# Adapter_v1_0B.net
KiCad netlist of a schematic drawn in EAGLE
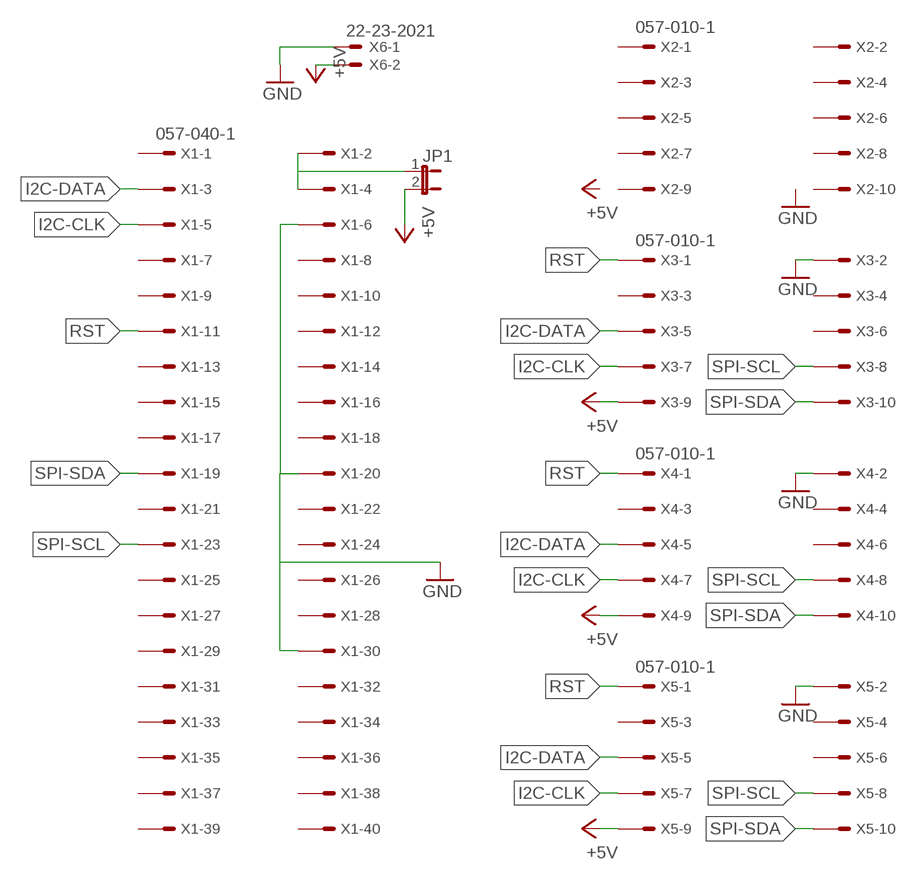
[diagram p0: schematic, sheet 1]

(export (version "E")
  (design (tool "Eeschema 10.0.6"))
  (components
    (comp (ref "JP1")
      (value "JP1E")
      (footprint "eagle-import:JP1")
      (libsource (lib "eagle-import") (part "JP1E"))
    )
    (comp (ref "X1")
      (value "057-040-1")
      (footprint "eagle-import:057-040-1")
      (libsource (lib "eagle-import") (part "057-040-1"))
    )
    (comp (ref "X2")
      (value "057-010-1")
      (footprint "eagle-import:057-010-1")
      (libsource (lib "eagle-import") (part "057-010-1"))
    )
    (comp (ref "X3")
      (value "057-010-1")
      (footprint "eagle-import:057-010-1")
      (libsource (lib "eagle-import") (part "057-010-1"))
    )
    (comp (ref "X4")
      (value "057-010-1")
      (footprint "eagle-import:057-010-1")
      (libsource (lib "eagle-import") (part "057-010-1"))
    )
    (comp (ref "X5")
      (value "057-010-1")
      (footprint "eagle-import:057-010-1")
      (libsource (lib "eagle-import") (part "057-010-1"))
    )
    (comp (ref "X6")
      (value "22-23-2021")
      (footprint "eagle-import:22-23-2021")
      (fields (field (name "MF") "MOLEX"))
      (libsource (lib "eagle-import") (part "22-23-2021"))
    )
  )
  (nets
    (net (code "1") (name "+5V") (class "Default")
      (node (ref "JP1") (pin "2") (pinfunction "2_2") (pintype "passive"))
      (node (ref "X3") (pin "9") (pinfunction "S_9") (pintype "passive"))
      (node (ref "X4") (pin "9") (pinfunction "S_9") (pintype "passive"))
      (node (ref "X5") (pin "9") (pinfunction "S_9") (pintype "passive"))
      (node (ref "X6") (pin "2") (pinfunction "S_2") (pintype "passive"))
    )
    (net (code "2") (name "GND") (class "Default")
      (node (ref "X1") (pin "20") (pinfunction "S_20") (pintype "passive"))
      (node (ref "X1") (pin "30") (pinfunction "S_30") (pintype "passive"))
      (node (ref "X1") (pin "6") (pinfunction "S_6") (pintype "passive"))
      (node (ref "X3") (pin "2") (pinfunction "S_2") (pintype "passive"))
      (node (ref "X4") (pin "2") (pinfunction "S_2") (pintype "passive"))
      (node (ref "X5") (pin "2") (pinfunction "S_2") (pintype "passive"))
      (node (ref "X6") (pin "1") (pinfunction "S_1") (pintype "passive"))
    )
    (net (code "3") (name "I2C-CLK") (class "Default")
      (node (ref "X1") (pin "5") (pinfunction "S_5") (pintype "passive"))
      (node (ref "X3") (pin "7") (pinfunction "S_7") (pintype "passive"))
      (node (ref "X4") (pin "7") (pinfunction "S_7") (pintype "passive"))
      (node (ref "X5") (pin "7") (pinfunction "S_7") (pintype "passive"))
    )
    (net (code "4") (name "I2C-DATA") (class "Default")
      (node (ref "X1") (pin "3") (pinfunction "S_3") (pintype "passive"))
      (node (ref "X3") (pin "5") (pinfunction "S_5") (pintype "passive"))
      (node (ref "X4") (pin "5") (pinfunction "S_5") (pintype "passive"))
      (node (ref "X5") (pin "5") (pinfunction "S_5") (pintype "passive"))
    )
    (net (code "5") (name "Net-(X1AH-S)") (class "Default")
      (node (ref "JP1") (pin "1") (pinfunction "1_1") (pintype "passive"))
      (node (ref "X1") (pin "2") (pinfunction "S_2") (pintype "passive"))
      (node (ref "X1") (pin "4") (pinfunction "S_4") (pintype "passive"))
    )
    (net (code "6") (name "RST") (class "Default")
      (node (ref "X1") (pin "11") (pinfunction "S_11") (pintype "passive"))
      (node (ref "X3") (pin "1") (pinfunction "S_1") (pintype "passive"))
      (node (ref "X4") (pin "1") (pinfunction "S_1") (pintype "passive"))
      (node (ref "X5") (pin "1") (pinfunction "S_1") (pintype "passive"))
    )
    (net (code "7") (name "SPI-SCL") (class "Default")
      (node (ref "X1") (pin "23") (pinfunction "S_23") (pintype "passive"))
      (node (ref "X3") (pin "8") (pinfunction "S_8") (pintype "passive"))
      (node (ref "X4") (pin "8") (pinfunction "S_8") (pintype "passive"))
      (node (ref "X5") (pin "8") (pinfunction "S_8") (pintype "passive"))
    )
    (net (code "8") (name "SPI-SDA") (class "Default")
      (node (ref "X1") (pin "19") (pinfunction "S_19") (pintype "passive"))
      (node (ref "X3") (pin "10") (pinfunction "S_10") (pintype "passive"))
      (node (ref "X4") (pin "10") (pinfunction "S_10") (pintype "passive"))
      (node (ref "X5") (pin "10") (pinfunction "S_10") (pintype "passive"))
    )
    (net (code "9") (name "unconnected-(X1A-S-Pad1)") (class "Default")
      (node (ref "X1") (pin "1") (pinfunction "S_1") (pintype "passive"))
    )
    (net (code "10") (name "unconnected-(X1AA-S-Pad33)") (class "Default")
      (node (ref "X1") (pin "33") (pinfunction "S_33") (pintype "passive"))
    )
    (net (code "11") (name "unconnected-(X1AB-S-Pad34)") (class "Default")
      (node (ref "X1") (pin "34") (pinfunction "S_34") (pintype "passive"))
    )
    (net (code "12") (name "unconnected-(X1AC-S-Pad35)") (class "Default")
      (node (ref "X1") (pin "35") (pinfunction "S_35") (pintype "passive"))
    )
    (net (code "13") (name "unconnected-(X1AD-S-Pad36)") (class "Default")
      (node (ref "X1") (pin "36") (pinfunction "S_36") (pintype "passive"))
    )
    (net (code "14") (name "unconnected-(X1AE-S-Pad37)") (class "Default")
      (node (ref "X1") (pin "37") (pinfunction "S_37") (pintype "passive"))
    )
    (net (code "15") (name "unconnected-(X1AF-S-Pad38)") (class "Default")
      (node (ref "X1") (pin "38") (pinfunction "S_38") (pintype "passive"))
    )
    (net (code "16") (name "unconnected-(X1AG-S-Pad39)") (class "Default")
      (node (ref "X1") (pin "39") (pinfunction "S_39") (pintype "passive"))
    )
    (net (code "17") (name "unconnected-(X1AI-S-Pad40)") (class "Default")
      (node (ref "X1") (pin "40") (pinfunction "S_40") (pintype "passive"))
    )
    (net (code "18") (name "unconnected-(X1AL-S-Pad7)") (class "Default")
      (node (ref "X1") (pin "7") (pinfunction "S_7") (pintype "passive"))
    )
    (net (code "19") (name "unconnected-(X1AM-S-Pad8)") (class "Default")
      (node (ref "X1") (pin "8") (pinfunction "S_8") (pintype "passive"))
    )
    (net (code "20") (name "unconnected-(X1AN-S-Pad9)") (class "Default")
      (node (ref "X1") (pin "9") (pinfunction "S_9") (pintype "passive"))
    )
    (net (code "21") (name "unconnected-(X1B-S-Pad10)") (class "Default")
      (node (ref "X1") (pin "10") (pinfunction "S_10") (pintype "passive"))
    )
    (net (code "22") (name "unconnected-(X1D-S-Pad12)") (class "Default")
      (node (ref "X1") (pin "12") (pinfunction "S_12") (pintype "passive"))
    )
    (net (code "23") (name "unconnected-(X1E-S-Pad13)") (class "Default")
      (node (ref "X1") (pin "13") (pinfunction "S_13") (pintype "passive"))
    )
    (net (code "24") (name "unconnected-(X1F-S-Pad14)") (class "Default")
      (node (ref "X1") (pin "14") (pinfunction "S_14") (pintype "passive"))
    )
    (net (code "25") (name "unconnected-(X1G-S-Pad15)") (class "Default")
      (node (ref "X1") (pin "15") (pinfunction "S_15") (pintype "passive"))
    )
    (net (code "26") (name "unconnected-(X1H-S-Pad16)") (class "Default")
      (node (ref "X1") (pin "16") (pinfunction "S_16") (pintype "passive"))
    )
    (net (code "27") (name "unconnected-(X1I-S-Pad17)") (class "Default")
      (node (ref "X1") (pin "17") (pinfunction "S_17") (pintype "passive"))
    )
    (net (code "28") (name "unconnected-(X1J-S-Pad18)") (class "Default")
      (node (ref "X1") (pin "18") (pinfunction "S_18") (pintype "passive"))
    )
    (net (code "29") (name "unconnected-(X1N-S-Pad21)") (class "Default")
      (node (ref "X1") (pin "21") (pinfunction "S_21") (pintype "passive"))
    )
    (net (code "30") (name "unconnected-(X1O-S-Pad22)") (class "Default")
      (node (ref "X1") (pin "22") (pinfunction "S_22") (pintype "passive"))
    )
    (net (code "31") (name "unconnected-(X1Q-S-Pad24)") (class "Default")
      (node (ref "X1") (pin "24") (pinfunction "S_24") (pintype "passive"))
    )
    (net (code "32") (name "unconnected-(X1R-S-Pad25)") (class "Default")
      (node (ref "X1") (pin "25") (pinfunction "S_25") (pintype "passive"))
    )
    (net (code "33") (name "unconnected-(X1S-S-Pad26)") (class "Default")
      (node (ref "X1") (pin "26") (pinfunction "S_26") (pintype "passive"))
    )
    (net (code "34") (name "unconnected-(X1T-S-Pad27)") (class "Default")
      (node (ref "X1") (pin "27") (pinfunction "S_27") (pintype "passive"))
    )
    (net (code "35") (name "unconnected-(X1U-S-Pad28)") (class "Default")
      (node (ref "X1") (pin "28") (pinfunction "S_28") (pintype "passive"))
    )
    (net (code "36") (name "unconnected-(X1V-S-Pad29)") (class "Default")
      (node (ref "X1") (pin "29") (pinfunction "S_29") (pintype "passive"))
    )
    (net (code "37") (name "unconnected-(X1Y-S-Pad31)") (class "Default")
      (node (ref "X1") (pin "31") (pinfunction "S_31") (pintype "passive"))
    )
    (net (code "38") (name "unconnected-(X1Z-S-Pad32)") (class "Default")
      (node (ref "X1") (pin "32") (pinfunction "S_32") (pintype "passive"))
    )
    (net (code "39") (name "unconnected-(X2A-S-Pad1)") (class "Default")
      (node (ref "X2") (pin "1") (pinfunction "S_1") (pintype "passive"))
    )
    (net (code "40") (name "unconnected-(X2B-S-Pad10)") (class "Default")
      (node (ref "X2") (pin "10") (pinfunction "S_10") (pintype "passive"))
    )
    (net (code "41") (name "unconnected-(X2C-S-Pad2)") (class "Default")
      (node (ref "X2") (pin "2") (pinfunction "S_2") (pintype "passive"))
    )
    (net (code "42") (name "unconnected-(X2D-S-Pad3)") (class "Default")
      (node (ref "X2") (pin "3") (pinfunction "S_3") (pintype "passive"))
    )
    (net (code "43") (name "unconnected-(X2E-S-Pad4)") (class "Default")
      (node (ref "X2") (pin "4") (pinfunction "S_4") (pintype "passive"))
    )
    (net (code "44") (name "unconnected-(X2F-S-Pad5)") (class "Default")
      (node (ref "X2") (pin "5") (pinfunction "S_5") (pintype "passive"))
    )
    (net (code "45") (name "unconnected-(X2G-S-Pad6)") (class "Default")
      (node (ref "X2") (pin "6") (pinfunction "S_6") (pintype "passive"))
    )
    (net (code "46") (name "unconnected-(X2H-S-Pad7)") (class "Default")
      (node (ref "X2") (pin "7") (pinfunction "S_7") (pintype "passive"))
    )
    (net (code "47") (name "unconnected-(X2I-S-Pad8)") (class "Default")
      (node (ref "X2") (pin "8") (pinfunction "S_8") (pintype "passive"))
    )
    (net (code "48") (name "unconnected-(X2J-S-Pad9)") (class "Default")
      (node (ref "X2") (pin "9") (pinfunction "S_9") (pintype "passive"))
    )
    (net (code "49") (name "unconnected-(X3D-S-Pad3)") (class "Default")
      (node (ref "X3") (pin "3") (pinfunction "S_3") (pintype "passive"))
    )
    (net (code "50") (name "unconnected-(X3E-S-Pad4)") (class "Default")
      (node (ref "X3") (pin "4") (pinfunction "S_4") (pintype "passive"))
    )
    (net (code "51") (name "unconnected-(X3G-S-Pad6)") (class "Default")
      (node (ref "X3") (pin "6") (pinfunction "S_6") (pintype "passive"))
    )
    (net (code "52") (name "unconnected-(X4D-S-Pad3)") (class "Default")
      (node (ref "X4") (pin "3") (pinfunction "S_3") (pintype "passive"))
    )
    (net (code "53") (name "unconnected-(X4E-S-Pad4)") (class "Default")
      (node (ref "X4") (pin "4") (pinfunction "S_4") (pintype "passive"))
    )
    (net (code "54") (name "unconnected-(X4G-S-Pad6)") (class "Default")
      (node (ref "X4") (pin "6") (pinfunction "S_6") (pintype "passive"))
    )
    (net (code "55") (name "unconnected-(X5D-S-Pad3)") (class "Default")
      (node (ref "X5") (pin "3") (pinfunction "S_3") (pintype "passive"))
    )
    (net (code "56") (name "unconnected-(X5E-S-Pad4)") (class "Default")
      (node (ref "X5") (pin "4") (pinfunction "S_4") (pintype "passive"))
    )
    (net (code "57") (name "unconnected-(X5G-S-Pad6)") (class "Default")
      (node (ref "X5") (pin "6") (pinfunction "S_6") (pintype "passive"))
    )
  )
)
